# M208C.net
KiCad netlist of a schematic drawn in EAGLE
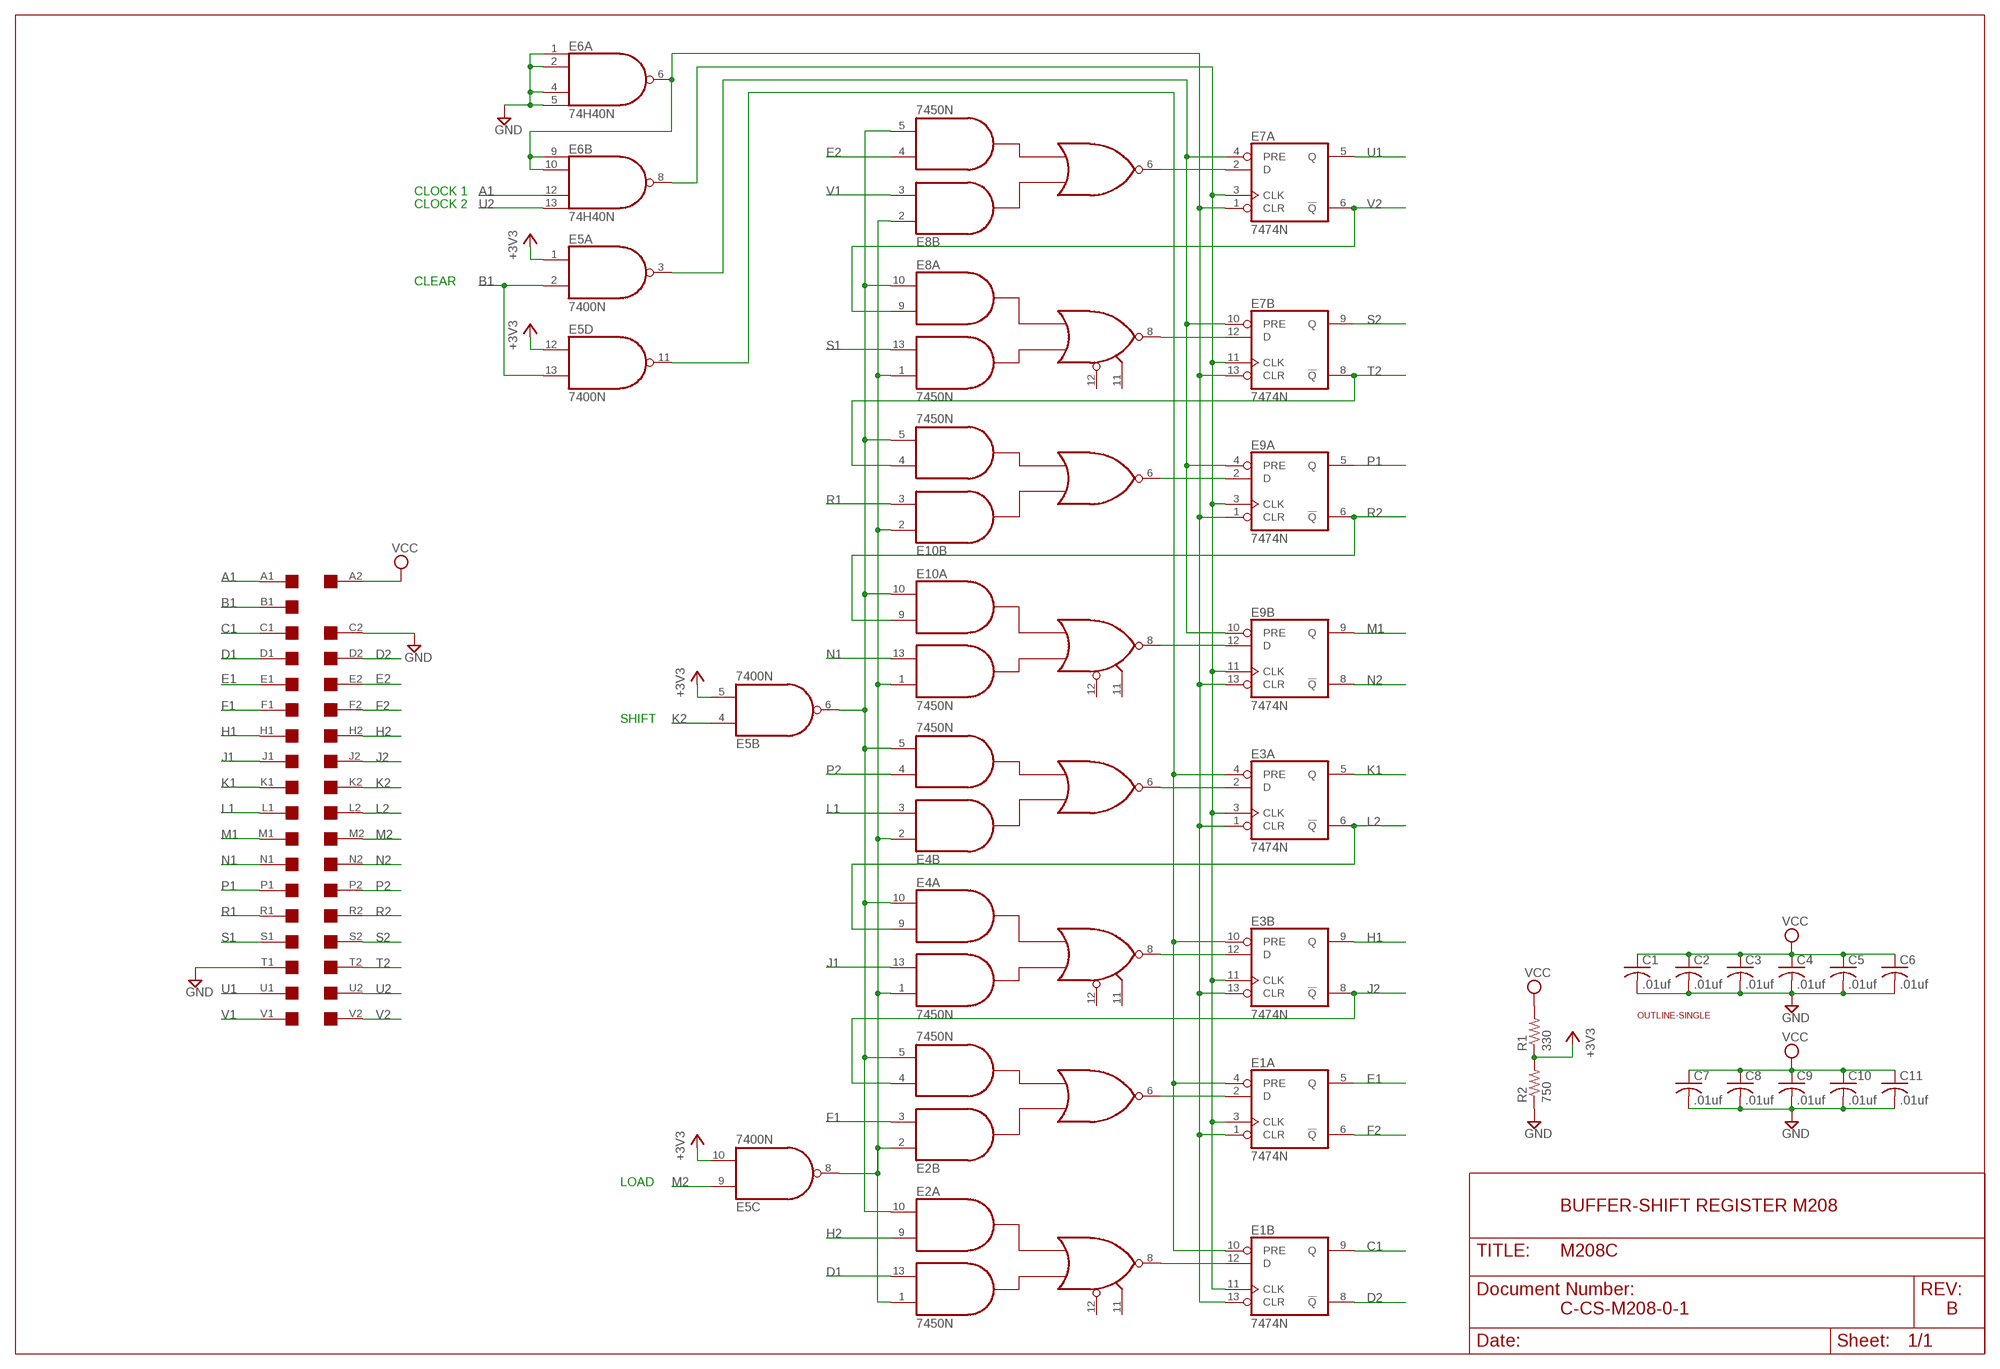
[diagram p0: schematic, sheet 1]

(export (version "E")
  (design (tool "Eeschema 10.0.6"))
  (components
    (comp (ref "C1")
      (value ".01uf")
      (footprint "eagle-import:C050-025X075")
      (libsource (lib "eagle-import") (part "C-US050-025X075"))
    )
    (comp (ref "C2")
      (value ".01uf")
      (footprint "eagle-import:C050-025X075")
      (libsource (lib "eagle-import") (part "C-US050-025X075"))
    )
    (comp (ref "C3")
      (value ".01uf")
      (footprint "eagle-import:C050-025X075")
      (libsource (lib "eagle-import") (part "C-US050-025X075"))
    )
    (comp (ref "C4")
      (value ".01uf")
      (footprint "eagle-import:C050-025X075")
      (libsource (lib "eagle-import") (part "C-US050-025X075"))
    )
    (comp (ref "C5")
      (value ".01uf")
      (footprint "eagle-import:C050-025X075")
      (libsource (lib "eagle-import") (part "C-US050-025X075"))
    )
    (comp (ref "C6")
      (value ".01uf")
      (footprint "eagle-import:C050-025X075")
      (libsource (lib "eagle-import") (part "C-US050-025X075"))
    )
    (comp (ref "C7")
      (value ".01uf")
      (footprint "eagle-import:C050-025X075")
      (libsource (lib "eagle-import") (part "C-US050-025X075"))
    )
    (comp (ref "C8")
      (value ".01uf")
      (footprint "eagle-import:C050-025X075")
      (libsource (lib "eagle-import") (part "C-US050-025X075"))
    )
    (comp (ref "C9")
      (value ".01uf")
      (footprint "eagle-import:C050-025X075")
      (libsource (lib "eagle-import") (part "C-US050-025X075"))
    )
    (comp (ref "C10")
      (value ".01uf")
      (footprint "eagle-import:C050-025X075")
      (libsource (lib "eagle-import") (part "C-US050-025X075"))
    )
    (comp (ref "C11")
      (value ".01uf")
      (footprint "eagle-import:C050-025X075")
      (libsource (lib "eagle-import") (part "C-US050-025X075"))
    )
    (comp (ref "E1")
      (value "7474N")
      (footprint "eagle-import:DIL14")
      (libsource (lib "eagle-import") (part "7474NS"))
    )
    (comp (ref "E2")
      (value "7450N")
      (footprint "eagle-import:DIL14")
      (libsource (lib "eagle-import") (part "7450N"))
    )
    (comp (ref "E3")
      (value "7474N")
      (footprint "eagle-import:DIL14")
      (libsource (lib "eagle-import") (part "7474NS"))
    )
    (comp (ref "E4")
      (value "7450N")
      (footprint "eagle-import:DIL14")
      (libsource (lib "eagle-import") (part "7450N"))
    )
    (comp (ref "E5")
      (value "7400N")
      (footprint "eagle-import:DIL14")
      (libsource (lib "eagle-import") (part "7400N"))
    )
    (comp (ref "E6")
      (value "74H40N")
      (footprint "eagle-import:DIL14")
      (libsource (lib "eagle-import") (part "7420NS"))
    )
    (comp (ref "E7")
      (value "7474N")
      (footprint "eagle-import:DIL14")
      (libsource (lib "eagle-import") (part "7474NS"))
    )
    (comp (ref "E8")
      (value "7450N")
      (footprint "eagle-import:DIL14")
      (libsource (lib "eagle-import") (part "7450N"))
    )
    (comp (ref "E9")
      (value "7474N")
      (footprint "eagle-import:DIL14")
      (libsource (lib "eagle-import") (part "7474NS"))
    )
    (comp (ref "E10")
      (value "7450N")
      (footprint "eagle-import:DIL14")
      (libsource (lib "eagle-import") (part "7450N"))
    )
    (comp (ref "R1")
      (value "330")
      (footprint "eagle-import:0207_10")
      (libsource (lib "eagle-import") (part "R-US_0207/10"))
    )
    (comp (ref "R2")
      (value "750")
      (footprint "eagle-import:0207_10")
      (libsource (lib "eagle-import") (part "R-US_0207/10"))
    )
    (comp (ref "U$1")
      (value "SINGLE")
      (footprint "eagle-import:EDGE-CON2")
      (libsource (lib "eagle-import") (part "SINGLE"))
    )
    (comp (ref "U$4")
      (value "OUTLINE-SINGLE")
      (footprint "eagle-import:SINGLE")
      (libsource (lib "eagle-import") (part "OUTLINE-SINGLE"))
    )
  )
  (nets
    (net (code "1") (name "+3V3") (class "Default")
      (node (ref "E5") (pin "1") (pinfunction "I0_1") (pintype "input"))
      (node (ref "E5") (pin "10") (pinfunction "I1_10") (pintype "input"))
      (node (ref "E5") (pin "12") (pinfunction "I0_12") (pintype "input"))
      (node (ref "E5") (pin "5") (pinfunction "I1_5") (pintype "input"))
      (node (ref "R1") (pin "1") (pinfunction "1_1") (pintype "passive"))
      (node (ref "R2") (pin "2") (pinfunction "2_2") (pintype "passive"))
    )
    (net (code "2") (name "/A1") (class "Default")
      (node (ref "E6") (pin "12") (pinfunction "I2_12") (pintype "input"))
      (node (ref "U$1") (pin "A1") (pinfunction "1_A1") (pintype "bidirectional"))
    )
    (net (code "3") (name "/B1") (class "Default")
      (node (ref "E5") (pin "13") (pinfunction "I1_13") (pintype "input"))
      (node (ref "E5") (pin "2") (pinfunction "I1_2") (pintype "input"))
      (node (ref "U$1") (pin "B1") (pinfunction "1_B1") (pintype "bidirectional"))
    )
    (net (code "4") (name "/C1") (class "Default")
      (node (ref "E1") (pin "9") (pinfunction "Q_9") (pintype "output"))
      (node (ref "U$1") (pin "C1") (pinfunction "1_C1") (pintype "bidirectional"))
    )
    (net (code "5") (name "/D1") (class "Default")
      (node (ref "E2") (pin "13") (pinfunction "I3_13") (pintype "input"))
      (node (ref "U$1") (pin "D1") (pinfunction "1_D1") (pintype "bidirectional"))
    )
    (net (code "6") (name "/D2") (class "Default")
      (node (ref "E1") (pin "8") (pinfunction "~{Q}_8") (pintype "output"))
      (node (ref "U$1") (pin "D2") (pinfunction "1_D2") (pintype "bidirectional"))
    )
    (net (code "7") (name "/E1") (class "Default")
      (node (ref "E1") (pin "5") (pinfunction "Q_5") (pintype "output"))
      (node (ref "U$1") (pin "E1") (pinfunction "1_E1") (pintype "bidirectional"))
    )
    (net (code "8") (name "/E2") (class "Default")
      (node (ref "E8") (pin "4") (pinfunction "I3_4") (pintype "input"))
      (node (ref "U$1") (pin "E2") (pinfunction "1_E2") (pintype "bidirectional"))
    )
    (net (code "9") (name "/F1") (class "Default")
      (node (ref "E2") (pin "3") (pinfunction "I2_3") (pintype "input"))
      (node (ref "U$1") (pin "F1") (pinfunction "1_F1") (pintype "bidirectional"))
    )
    (net (code "10") (name "/F2") (class "Default")
      (node (ref "E1") (pin "6") (pinfunction "~{Q}_6") (pintype "output"))
      (node (ref "U$1") (pin "F2") (pinfunction "1_F2") (pintype "bidirectional"))
    )
    (net (code "11") (name "/H1") (class "Default")
      (node (ref "E3") (pin "9") (pinfunction "Q_9") (pintype "output"))
      (node (ref "U$1") (pin "H1") (pinfunction "1_H1") (pintype "bidirectional"))
    )
    (net (code "12") (name "/H2") (class "Default")
      (node (ref "E2") (pin "9") (pinfunction "I2_9") (pintype "input"))
      (node (ref "U$1") (pin "H2") (pinfunction "1_H2") (pintype "bidirectional"))
    )
    (net (code "13") (name "/J1") (class "Default")
      (node (ref "E4") (pin "13") (pinfunction "I3_13") (pintype "input"))
      (node (ref "U$1") (pin "J1") (pinfunction "1_J1") (pintype "bidirectional"))
    )
    (net (code "14") (name "/J2") (class "Default")
      (node (ref "E2") (pin "4") (pinfunction "I3_4") (pintype "input"))
      (node (ref "E3") (pin "8") (pinfunction "~{Q}_8") (pintype "output"))
      (node (ref "U$1") (pin "J2") (pinfunction "1_J2") (pintype "bidirectional"))
    )
    (net (code "15") (name "/K1") (class "Default")
      (node (ref "E3") (pin "5") (pinfunction "Q_5") (pintype "output"))
      (node (ref "U$1") (pin "K1") (pinfunction "1_K1") (pintype "bidirectional"))
    )
    (net (code "16") (name "/K2") (class "Default")
      (node (ref "E5") (pin "4") (pinfunction "I0_4") (pintype "input"))
      (node (ref "U$1") (pin "K2") (pinfunction "1_K2") (pintype "bidirectional"))
    )
    (net (code "17") (name "/L1") (class "Default")
      (node (ref "E4") (pin "3") (pinfunction "I2_3") (pintype "input"))
      (node (ref "U$1") (pin "L1") (pinfunction "1_L1") (pintype "bidirectional"))
    )
    (net (code "18") (name "/L2") (class "Default")
      (node (ref "E3") (pin "6") (pinfunction "~{Q}_6") (pintype "output"))
      (node (ref "E4") (pin "9") (pinfunction "I2_9") (pintype "input"))
      (node (ref "U$1") (pin "L2") (pinfunction "1_L2") (pintype "bidirectional"))
    )
    (net (code "19") (name "/M1") (class "Default")
      (node (ref "E9") (pin "9") (pinfunction "Q_9") (pintype "output"))
      (node (ref "U$1") (pin "M1") (pinfunction "1_M1") (pintype "bidirectional"))
    )
    (net (code "20") (name "/M2") (class "Default")
      (node (ref "E5") (pin "9") (pinfunction "I0_9") (pintype "input"))
      (node (ref "U$1") (pin "M2") (pinfunction "1_M2") (pintype "bidirectional"))
    )
    (net (code "21") (name "/N1") (class "Default")
      (node (ref "E10") (pin "13") (pinfunction "I3_13") (pintype "input"))
      (node (ref "U$1") (pin "N1") (pinfunction "1_N1") (pintype "bidirectional"))
    )
    (net (code "22") (name "/N2") (class "Default")
      (node (ref "E9") (pin "8") (pinfunction "~{Q}_8") (pintype "output"))
      (node (ref "U$1") (pin "N2") (pinfunction "1_N2") (pintype "bidirectional"))
    )
    (net (code "23") (name "/P1") (class "Default")
      (node (ref "E9") (pin "5") (pinfunction "Q_5") (pintype "output"))
      (node (ref "U$1") (pin "P1") (pinfunction "1_P1") (pintype "bidirectional"))
    )
    (net (code "24") (name "/P2") (class "Default")
      (node (ref "E4") (pin "4") (pinfunction "I3_4") (pintype "input"))
      (node (ref "U$1") (pin "P2") (pinfunction "1_P2") (pintype "bidirectional"))
    )
    (net (code "25") (name "/R1") (class "Default")
      (node (ref "E10") (pin "3") (pinfunction "I2_3") (pintype "input"))
      (node (ref "U$1") (pin "R1") (pinfunction "1_R1") (pintype "bidirectional"))
    )
    (net (code "26") (name "/R2") (class "Default")
      (node (ref "E10") (pin "9") (pinfunction "I2_9") (pintype "input"))
      (node (ref "E9") (pin "6") (pinfunction "~{Q}_6") (pintype "output"))
      (node (ref "U$1") (pin "R2") (pinfunction "1_R2") (pintype "bidirectional"))
    )
    (net (code "27") (name "/S1") (class "Default")
      (node (ref "E8") (pin "13") (pinfunction "I3_13") (pintype "input"))
      (node (ref "U$1") (pin "S1") (pinfunction "1_S1") (pintype "bidirectional"))
    )
    (net (code "28") (name "/S2") (class "Default")
      (node (ref "E7") (pin "9") (pinfunction "Q_9") (pintype "output"))
      (node (ref "U$1") (pin "S2") (pinfunction "1_S2") (pintype "bidirectional"))
    )
    (net (code "29") (name "/T2") (class "Default")
      (node (ref "E10") (pin "4") (pinfunction "I3_4") (pintype "input"))
      (node (ref "E7") (pin "8") (pinfunction "~{Q}_8") (pintype "output"))
      (node (ref "U$1") (pin "T2") (pinfunction "1_T2") (pintype "bidirectional"))
    )
    (net (code "30") (name "/U1") (class "Default")
      (node (ref "E7") (pin "5") (pinfunction "Q_5") (pintype "output"))
      (node (ref "U$1") (pin "U1") (pinfunction "1_U1") (pintype "bidirectional"))
    )
    (net (code "31") (name "/U2") (class "Default")
      (node (ref "E6") (pin "13") (pinfunction "I3_13") (pintype "input"))
      (node (ref "U$1") (pin "U2") (pinfunction "1_U2") (pintype "bidirectional"))
    )
    (net (code "32") (name "/V1") (class "Default")
      (node (ref "E8") (pin "3") (pinfunction "I2_3") (pintype "input"))
      (node (ref "U$1") (pin "V1") (pinfunction "1_V1") (pintype "bidirectional"))
    )
    (net (code "33") (name "/V2") (class "Default")
      (node (ref "E7") (pin "6") (pinfunction "~{Q}_6") (pintype "output"))
      (node (ref "E8") (pin "9") (pinfunction "I2_9") (pintype "input"))
      (node (ref "U$1") (pin "V2") (pinfunction "1_V2") (pintype "bidirectional"))
    )
    (net (code "34") (name "GND") (class "Default")
      (node (ref "C1") (pin "2") (pinfunction "2_2") (pintype "passive"))
      (node (ref "C10") (pin "2") (pinfunction "2_2") (pintype "passive"))
      (node (ref "C11") (pin "2") (pinfunction "2_2") (pintype "passive"))
      (node (ref "C2") (pin "2") (pinfunction "2_2") (pintype "passive"))
      (node (ref "C3") (pin "2") (pinfunction "2_2") (pintype "passive"))
      (node (ref "C4") (pin "2") (pinfunction "2_2") (pintype "passive"))
      (node (ref "C5") (pin "2") (pinfunction "2_2") (pintype "passive"))
      (node (ref "C6") (pin "2") (pinfunction "2_2") (pintype "passive"))
      (node (ref "C7") (pin "2") (pinfunction "2_2") (pintype "passive"))
      (node (ref "C8") (pin "2") (pinfunction "2_2") (pintype "passive"))
      (node (ref "C9") (pin "2") (pinfunction "2_2") (pintype "passive"))
      (node (ref "E6") (pin "1") (pinfunction "I0_1") (pintype "input"))
      (node (ref "E6") (pin "2") (pinfunction "I1_2") (pintype "input"))
      (node (ref "E6") (pin "4") (pinfunction "I2_4") (pintype "input"))
      (node (ref "E6") (pin "5") (pinfunction "I3_5") (pintype "input"))
      (node (ref "R2") (pin "1") (pinfunction "1_1") (pintype "passive"))
      (node (ref "U$1") (pin "C2") (pinfunction "1_C2") (pintype "bidirectional"))
      (node (ref "U$1") (pin "T1") (pinfunction "1_T1") (pintype "bidirectional"))
    )
    (net (code "35") (name "Net-(E1A-CLK)") (class "Default")
      (node (ref "E1") (pin "11") (pinfunction "CLK_11") (pintype "input"))
      (node (ref "E1") (pin "3") (pinfunction "CLK_3") (pintype "input"))
      (node (ref "E3") (pin "11") (pinfunction "CLK_11") (pintype "input"))
      (node (ref "E3") (pin "3") (pinfunction "CLK_3") (pintype "input"))
      (node (ref "E6") (pin "8") (pinfunction "O_8") (pintype "output"))
      (node (ref "E7") (pin "11") (pinfunction "CLK_11") (pintype "input"))
      (node (ref "E7") (pin "3") (pinfunction "CLK_3") (pintype "input"))
      (node (ref "E9") (pin "11") (pinfunction "CLK_11") (pintype "input"))
      (node (ref "E9") (pin "3") (pinfunction "CLK_3") (pintype "input"))
    )
    (net (code "36") (name "Net-(E1A-CLR)") (class "Default")
      (node (ref "E1") (pin "1") (pinfunction "CLR_1") (pintype "input"))
      (node (ref "E1") (pin "13") (pinfunction "CLR_13") (pintype "input"))
      (node (ref "E3") (pin "1") (pinfunction "CLR_1") (pintype "input"))
      (node (ref "E3") (pin "13") (pinfunction "CLR_13") (pintype "input"))
      (node (ref "E6") (pin "10") (pinfunction "I1_10") (pintype "input"))
      (node (ref "E6") (pin "6") (pinfunction "O_6") (pintype "output"))
      (node (ref "E6") (pin "9") (pinfunction "I0_9") (pintype "input"))
      (node (ref "E7") (pin "1") (pinfunction "CLR_1") (pintype "input"))
      (node (ref "E7") (pin "13") (pinfunction "CLR_13") (pintype "input"))
      (node (ref "E9") (pin "1") (pinfunction "CLR_1") (pintype "input"))
      (node (ref "E9") (pin "13") (pinfunction "CLR_13") (pintype "input"))
    )
    (net (code "37") (name "Net-(E1A-D)") (class "Default")
      (node (ref "E1") (pin "2") (pinfunction "D_2") (pintype "input"))
      (node (ref "E2") (pin "6") (pinfunction "O_6") (pintype "output"))
    )
    (net (code "38") (name "Net-(E1A-PRE)") (class "Default")
      (node (ref "E1") (pin "10") (pinfunction "PRE_10") (pintype "input"))
      (node (ref "E1") (pin "4") (pinfunction "PRE_4") (pintype "input"))
      (node (ref "E3") (pin "10") (pinfunction "PRE_10") (pintype "input"))
      (node (ref "E3") (pin "4") (pinfunction "PRE_4") (pintype "input"))
      (node (ref "E5") (pin "11") (pinfunction "O_11") (pintype "output"))
    )
    (net (code "39") (name "Net-(E1B-D)") (class "Default")
      (node (ref "E1") (pin "12") (pinfunction "D_12") (pintype "input"))
      (node (ref "E2") (pin "8") (pinfunction "O_8") (pintype "output"))
    )
    (net (code "40") (name "Net-(E3A-D)") (class "Default")
      (node (ref "E3") (pin "2") (pinfunction "D_2") (pintype "input"))
      (node (ref "E4") (pin "6") (pinfunction "O_6") (pintype "output"))
    )
    (net (code "41") (name "Net-(E3B-D)") (class "Default")
      (node (ref "E3") (pin "12") (pinfunction "D_12") (pintype "input"))
      (node (ref "E4") (pin "8") (pinfunction "O_8") (pintype "output"))
    )
    (net (code "42") (name "Net-(E5A-O)") (class "Default")
      (node (ref "E5") (pin "3") (pinfunction "O_3") (pintype "output"))
      (node (ref "E7") (pin "10") (pinfunction "PRE_10") (pintype "input"))
      (node (ref "E7") (pin "4") (pinfunction "PRE_4") (pintype "input"))
      (node (ref "E9") (pin "10") (pinfunction "PRE_10") (pintype "input"))
      (node (ref "E9") (pin "4") (pinfunction "PRE_4") (pintype "input"))
    )
    (net (code "43") (name "Net-(E7A-D)") (class "Default")
      (node (ref "E7") (pin "2") (pinfunction "D_2") (pintype "input"))
      (node (ref "E8") (pin "6") (pinfunction "O_6") (pintype "output"))
    )
    (net (code "44") (name "Net-(E7B-D)") (class "Default")
      (node (ref "E7") (pin "12") (pinfunction "D_12") (pintype "input"))
      (node (ref "E8") (pin "8") (pinfunction "O_8") (pintype "output"))
    )
    (net (code "45") (name "Net-(E10A-I1)") (class "Default")
      (node (ref "E10") (pin "10") (pinfunction "I1_10") (pintype "input"))
      (node (ref "E10") (pin "5") (pinfunction "I4_5") (pintype "input"))
      (node (ref "E2") (pin "10") (pinfunction "I1_10") (pintype "input"))
      (node (ref "E2") (pin "5") (pinfunction "I4_5") (pintype "input"))
      (node (ref "E4") (pin "10") (pinfunction "I1_10") (pintype "input"))
      (node (ref "E4") (pin "5") (pinfunction "I4_5") (pintype "input"))
      (node (ref "E5") (pin "6") (pinfunction "O_6") (pintype "output"))
      (node (ref "E8") (pin "10") (pinfunction "I1_10") (pintype "input"))
      (node (ref "E8") (pin "5") (pinfunction "I4_5") (pintype "input"))
    )
    (net (code "46") (name "Net-(E10A-I4)") (class "Default")
      (node (ref "E10") (pin "1") (pinfunction "I4_1") (pintype "input"))
      (node (ref "E10") (pin "2") (pinfunction "I1_2") (pintype "input"))
      (node (ref "E2") (pin "1") (pinfunction "I4_1") (pintype "input"))
      (node (ref "E2") (pin "2") (pinfunction "I1_2") (pintype "input"))
      (node (ref "E4") (pin "1") (pinfunction "I4_1") (pintype "input"))
      (node (ref "E4") (pin "2") (pinfunction "I1_2") (pintype "input"))
      (node (ref "E5") (pin "8") (pinfunction "O_8") (pintype "output"))
      (node (ref "E8") (pin "1") (pinfunction "I4_1") (pintype "input"))
      (node (ref "E8") (pin "2") (pinfunction "I1_2") (pintype "input"))
    )
    (net (code "47") (name "Net-(E10A-O)") (class "Default")
      (node (ref "E10") (pin "8") (pinfunction "O_8") (pintype "output"))
      (node (ref "E9") (pin "12") (pinfunction "D_12") (pintype "input"))
    )
    (net (code "48") (name "Net-(E10B-O)") (class "Default")
      (node (ref "E10") (pin "6") (pinfunction "O_6") (pintype "output"))
      (node (ref "E9") (pin "2") (pinfunction "D_2") (pintype "input"))
    )
    (net (code "49") (name "VCC") (class "Default")
      (node (ref "C1") (pin "1") (pinfunction "1_1") (pintype "passive"))
      (node (ref "C10") (pin "1") (pinfunction "1_1") (pintype "passive"))
      (node (ref "C11") (pin "1") (pinfunction "1_1") (pintype "passive"))
      (node (ref "C2") (pin "1") (pinfunction "1_1") (pintype "passive"))
      (node (ref "C3") (pin "1") (pinfunction "1_1") (pintype "passive"))
      (node (ref "C4") (pin "1") (pinfunction "1_1") (pintype "passive"))
      (node (ref "C5") (pin "1") (pinfunction "1_1") (pintype "passive"))
      (node (ref "C6") (pin "1") (pinfunction "1_1") (pintype "passive"))
      (node (ref "C7") (pin "1") (pinfunction "1_1") (pintype "passive"))
      (node (ref "C8") (pin "1") (pinfunction "1_1") (pintype "passive"))
      (node (ref "C9") (pin "1") (pinfunction "1_1") (pintype "passive"))
      (node (ref "R1") (pin "2") (pinfunction "2_2") (pintype "passive"))
      (node (ref "U$1") (pin "A2") (pinfunction "1_A2") (pintype "bidirectional"))
    )
    (net (code "50") (name "unconnected-(E2A-I5-Pad12)") (class "Default")
      (node (ref "E2") (pin "12") (pinfunction "I5_12") (pintype "passive"))
    )
    (net (code "51") (name "unconnected-(E2A-I6-Pad11)") (class "Default")
      (node (ref "E2") (pin "11") (pinfunction "I6_11") (pintype "passive"))
    )
    (net (code "52") (name "unconnected-(E4A-I5-Pad12)") (class "Default")
      (node (ref "E4") (pin "12") (pinfunction "I5_12") (pintype "passive"))
    )
    (net (code "53") (name "unconnected-(E4A-I6-Pad11)") (class "Default")
      (node (ref "E4") (pin "11") (pinfunction "I6_11") (pintype "passive"))
    )
    (net (code "54") (name "unconnected-(E8A-I5-Pad12)") (class "Default")
      (node (ref "E8") (pin "12") (pinfunction "I5_12") (pintype "passive"))
    )
    (net (code "55") (name "unconnected-(E8A-I6-Pad11)") (class "Default")
      (node (ref "E8") (pin "11") (pinfunction "I6_11") (pintype "passive"))
    )
    (net (code "56") (name "unconnected-(E10A-I5-Pad12)") (class "Default")
      (node (ref "E10") (pin "12") (pinfunction "I5_12") (pintype "passive"))
    )
    (net (code "57") (name "unconnected-(E10A-I6-Pad11)") (class "Default")
      (node (ref "E10") (pin "11") (pinfunction "I6_11") (pintype "passive"))
    )
  )
)
